# TPS54302-4V.net
KiCad netlist of a schematic drawn in Altium Designer
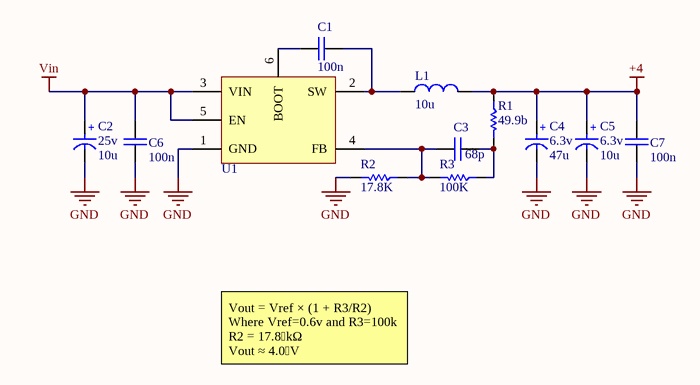
[diagram p0: TPS54302-4V.SchDoc]

(export (version "E")
  (design (tool "Eeschema 10.0.6"))
  (components
    (comp (ref "C1")
      (value "100n")
      (footprint "CAP 0805/2012")
      (description "Bipolar ceramic capacitor SMD")
      (fields (field (name "VALIDATION") "Valid"))
      (libsource (lib "aKaReZa") (part "Cap_Multi_SMD_100nF_0805"))
    )
    (comp (ref "C2")
      (value "10u")
      (footprint "SMT_C_Tantalum_B")
      (description "Tantalum Capacitor,TAJ Series-SMD")
      (fields (field (name "RATING") "25v") (field (name "VALIDATION") "Valid"))
      (libsource (lib "aKaReZa") (part "Cap_Tantalum"))
    )
    (comp (ref "C3")
      (value "68p")
      (footprint "CAP 0805/2012")
      (description "Bipolar ceramic capacitor SMD")
      (fields (field (name "VALIDATION") "Valid"))
      (libsource (lib "aKaReZa") (part "Cap_Multi_SMD_0805"))
    )
    (comp (ref "C4")
      (value "47u")
      (footprint "SMT_C_Tantalum_B")
      (description "Tantalum Capacitor,TAJ Series-SMD")
      (fields (field (name "RATING") "6.3v") (field (name "VALIDATION") "Valid"))
      (libsource (lib "aKaReZa") (part "Cap_Tantalum"))
    )
    (comp (ref "C5")
      (value "10u")
      (footprint "SMT_C_Tantalum_A")
      (description "Tantalum Capacitor,TAJ Series-SMD")
      (fields (field (name "RATING") "6.3v") (field (name "VALIDATION") "Valid"))
      (libsource (lib "aKaReZa") (part "Cap_Tantalum"))
    )
    (comp (ref "C6")
      (value "100n")
      (footprint "CAP 1206/3216")
      (description "Bipolar ceramic capacitor SMD")
      (fields (field (name "VALIDATION") "Valid"))
      (libsource (lib "aKaReZa") (part "Cap_Multi_SMD_100nF_1206"))
    )
    (comp (ref "C7")
      (value "100n")
      (footprint "CAP 1206/3216")
      (description "Bipolar ceramic capacitor SMD")
      (fields (field (name "VALIDATION") "Valid"))
      (libsource (lib "aKaReZa") (part "Cap_Multi_SMD_100nF_1206"))
    )
    (comp (ref "L1")
      (value "10u")
      (footprint "L_7")
      (description "Inductor")
      (fields (field (name "VALIDATION") "Valid"))
      (libsource (lib "aKaReZa") (part "Ind_SMD"))
    )
    (comp (ref "R1")
      (value "49.9b")
      (footprint "RES 0805 (2012X06L)")
      (description "Resistor")
      (fields (field (name "VALIDATION") "Valid"))
      (libsource (lib "aKaReZa") (part "Res_SMD_0805"))
    )
    (comp (ref "R2")
      (value "17.8K")
      (footprint "RES 0805 (2012X06L)")
      (description "Resistor")
      (fields (field (name "VALIDATION") "Valid"))
      (libsource (lib "aKaReZa") (part "Res_SMD_0805"))
    )
    (comp (ref "R3")
      (value "100K")
      (footprint "RES 0805 (2012X06L)")
      (description "Resistor")
      (fields (field (name "VALIDATION") "Valid"))
      (libsource (lib "aKaReZa") (part "Res_SMD_0805"))
    )
    (comp (ref "U1")
      (value "Value?")
      (footprint "TPS54302")
      (description "3'A Synchronous Step-Down Converter")
      (fields (field (name "VALIDATION") "Valid"))
      (libsource (lib "aKaReZa") (part "IC_Reg_TPS54302"))
    )
  )
  (nets
    (net (code "1") (name "+4") (class "Default")
      (node (ref "C4") (pin "1") (pinfunction "+_1") (pintype "passive"))
      (node (ref "C5") (pin "1") (pinfunction "+_1") (pintype "passive"))
      (node (ref "C7") (pin "1") (pinfunction "1_1") (pintype "passive"))
      (node (ref "L1") (pin "2") (pinfunction "2_2") (pintype "passive"))
      (node (ref "R1") (pin "1") (pinfunction "1_1") (pintype "passive"))
    )
    (net (code "2") (name "GND") (class "Default")
      (node (ref "C2") (pin "2") (pinfunction "-_2") (pintype "passive"))
      (node (ref "C4") (pin "2") (pinfunction "-_2") (pintype "passive"))
      (node (ref "C5") (pin "2") (pinfunction "-_2") (pintype "passive"))
      (node (ref "C6") (pin "2") (pinfunction "2_2") (pintype "passive"))
      (node (ref "C7") (pin "2") (pinfunction "2_2") (pintype "passive"))
      (node (ref "R2") (pin "2") (pinfunction "2_2") (pintype "passive"))
      (node (ref "U1") (pin "1") (pinfunction "GND_1") (pintype "power_in"))
    )
    (net (code "3") (name "Net-(C3-Pad2)") (class "Default")
      (node (ref "C3") (pin "2") (pinfunction "2_2") (pintype "passive"))
      (node (ref "R1") (pin "2") (pinfunction "2_2") (pintype "passive"))
      (node (ref "R3") (pin "1") (pinfunction "1_1") (pintype "passive"))
    )
    (net (code "4") (name "Net-(U1-BOOT)") (class "Default")
      (node (ref "C1") (pin "1") (pinfunction "1_1") (pintype "passive"))
      (node (ref "U1") (pin "6") (pinfunction "BOOT_6") (pintype "power_in"))
    )
    (net (code "5") (name "Net-(U1-FB)") (class "Default")
      (node (ref "C3") (pin "1") (pinfunction "1_1") (pintype "passive"))
      (node (ref "R2") (pin "1") (pinfunction "1_1") (pintype "passive"))
      (node (ref "R3") (pin "2") (pinfunction "2_2") (pintype "passive"))
      (node (ref "U1") (pin "4") (pinfunction "FB_4") (pintype "power_in"))
    )
    (net (code "6") (name "Net-(U1-SW)") (class "Default")
      (node (ref "C1") (pin "2") (pinfunction "2_2") (pintype "passive"))
      (node (ref "L1") (pin "1") (pinfunction "1_1") (pintype "passive"))
      (node (ref "U1") (pin "2") (pinfunction "SW_2") (pintype "power_in"))
    )
    (net (code "7") (name "Vin") (class "Default")
      (node (ref "C2") (pin "1") (pinfunction "+_1") (pintype "passive"))
      (node (ref "C6") (pin "1") (pinfunction "1_1") (pintype "passive"))
      (node (ref "U1") (pin "3") (pinfunction "VIN_3") (pintype "power_in"))
      (node (ref "U1") (pin "5") (pinfunction "EN_5") (pintype "power_in"))
    )
  )
)
